# Sheet1.net
KiCad netlist of a schematic drawn in Altium Designer
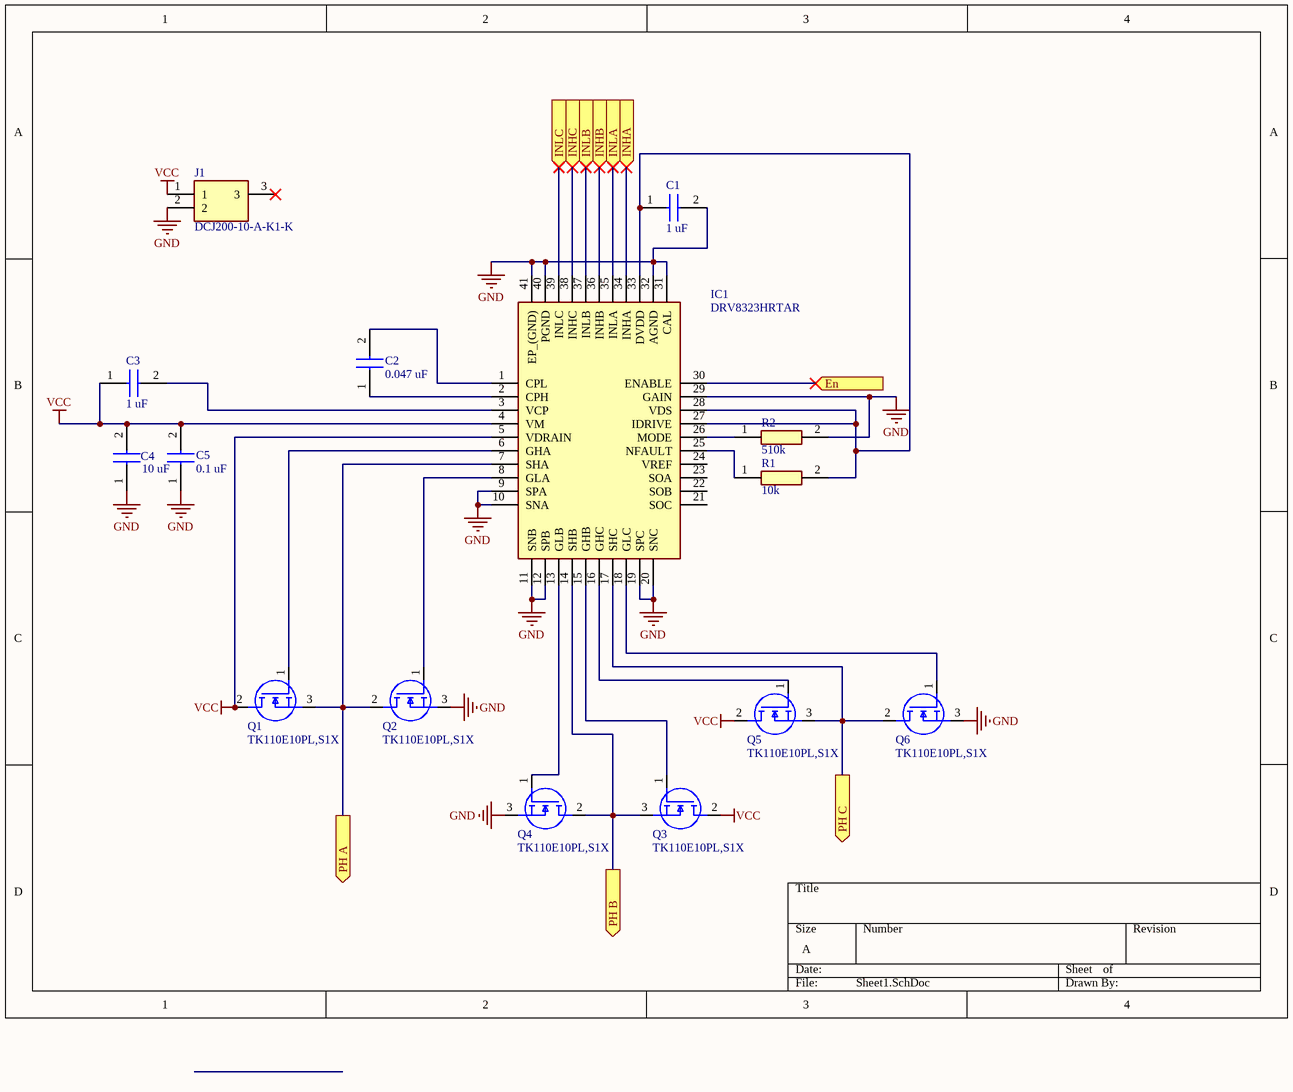
[diagram p0: Sheet1.SchDoc]

(export (version "E")
  (design (tool "Eeschema 10.0.6"))
  (components
    (comp (ref "C1")
      (value "1 uF")
      (footprint "SamacSys:INDC1608X90N")
      (description "Capacitor")
      (fields
        (field (name "MANUFACTURER_PART_NUMBER") "UMK107BJ105KA-T")
        (field (name "MOUSER PART NUMBER") "963-UMK107BJ105KA-T")
      )
      (libsource (lib "*") (part "UMK107BJ105KA-T"))
    )
    (comp (ref "C2")
      (value "0.047 uF")
      (footprint "SamacSys:C0603")
      (description "Capacitor")
      (fields
        (field (name "MANUFACTURER_PART_NUMBER") "C0603C473K5RACTU")
        (field (name "MOUSER PART NUMBER") "80-C0603C473K5R")
      )
      (libsource (lib "*") (part "C0603C473K5RACTU"))
    )
    (comp (ref "C3")
      (value "1 uF")
      (footprint "SamacSys:INDC1608X90N")
      (description "Capacitor")
      (fields
        (field (name "MANUFACTURER_PART_NUMBER") "UMK107BJ105KA-T")
        (field (name "MOUSER PART NUMBER") "963-UMK107BJ105KA-T")
      )
      (libsource (lib "*") (part "UMK107BJ105KA-T"))
    )
    (comp (ref "C4")
      (value "10 uF")
      (footprint "SamacSys:CAPC3216X180N")
      (description "Capacitor")
      (fields
        (field (name "MANUFACTURER_PART_NUMBER") "CL31B106KBHNNNE")
        (field (name "MOUSER PART NUMBER") "187-CL31B106KBHNNNE")
      )
      (libsource (lib "*") (part "CL31B106KBHNNNE"))
    )
    (comp (ref "C5")
      (value "0.1 uF")
      (footprint "SamacSys:CAPC1608X95N")
      (description "Capacitor")
      (fields (field (name "MANUFACTURER_PART_NUMBER") "C0603C104K5RACTU7042"))
      (libsource (lib "*") (part "C0603C104K5RACTU7042"))
    )
    (comp (ref "IC1")
      (value "DRV8323HRTAR")
      (footprint "SamacSys:QFN50P600X600X80-41N-D")
      (description "Integrated Circuit")
      (fields (field (name "MOUSER PART NUMBER") "595-DRV8323HRTAR"))
      (libsource (lib "*") (part "DRV8323HRTAR"))
    )
    (comp (ref "J1")
      (value "DCJ200-10-A-K1-K")
      (footprint "SamacSys:DCJ20010AK1K")
      (description "Connector")
      (fields (field (name "MOUSER PART NUMBER") "640-DCJ200-10-A-K1-K"))
      (libsource (lib "*") (part "DCJ200-10-A-K1-K"))
    )
    (comp (ref "Q1")
      (value "TK110E10PL,S1X")
      (footprint "SamacSys:TO254P465X1016X1935-3P")
      (description "MOSFET (N-Channel)")
      (fields (field (name "MOUSER PART NUMBER") "757-TK110E10PLS1X"))
      (libsource (lib "*") (part "TK110E10PL,S1X"))
    )
    (comp (ref "Q2")
      (value "TK110E10PL,S1X")
      (footprint "SamacSys:TO254P465X1016X1935-3P")
      (description "MOSFET (N-Channel)")
      (fields (field (name "MOUSER PART NUMBER") "757-TK110E10PLS1X"))
      (libsource (lib "*") (part "TK110E10PL,S1X"))
    )
    (comp (ref "Q3")
      (value "TK110E10PL,S1X")
      (footprint "SamacSys:TO254P465X1016X1935-3P")
      (description "MOSFET (N-Channel)")
      (fields (field (name "MOUSER PART NUMBER") "757-TK110E10PLS1X"))
      (libsource (lib "*") (part "TK110E10PL,S1X"))
    )
    (comp (ref "Q4")
      (value "TK110E10PL,S1X")
      (footprint "SamacSys:TO254P465X1016X1935-3P")
      (description "MOSFET (N-Channel)")
      (fields (field (name "MOUSER PART NUMBER") "757-TK110E10PLS1X"))
      (libsource (lib "*") (part "TK110E10PL,S1X"))
    )
    (comp (ref "Q5")
      (value "TK110E10PL,S1X")
      (footprint "SamacSys:TO254P465X1016X1935-3P")
      (description "MOSFET (N-Channel)")
      (fields (field (name "MOUSER PART NUMBER") "757-TK110E10PLS1X"))
      (libsource (lib "*") (part "TK110E10PL,S1X"))
    )
    (comp (ref "Q6")
      (value "TK110E10PL,S1X")
      (footprint "SamacSys:TO254P465X1016X1935-3P")
      (description "MOSFET (N-Channel)")
      (fields (field (name "MOUSER PART NUMBER") "757-TK110E10PLS1X"))
      (libsource (lib "*") (part "TK110E10PL,S1X"))
    )
    (comp (ref "R1")
      (value "10k")
      (footprint "SamacSys:RESC2012X50N")
      (description "Resistor 10K")
      (fields
        (field (name "MANUFACTURER_PART_NUMBER") "CRCW080510K0FKEA")
        (field (name "MOUSER PART NUMBER") "71-CRCW0805-10K-E3")
      )
      (libsource (lib "*") (part "CRCW080510K0FKEA"))
    )
    (comp (ref "R2")
      (value "510k")
      (footprint "SamacSys:RESC3116X65N")
      (description "Resistor 510K")
      (fields
        (field (name "MANUFACTURER_PART_NUMBER") "RC1206FR-07510KL")
        (field (name "MOUSER PART NUMBER") "603-RC1206FR-07510KL")
      )
      (libsource (lib "*") (part "RC1206FR-07510KL"))
    )
  )
  (nets
    (net (code "1") (name "/En") (class "Default")
      (node (ref "IC1") (pin "30") (pinfunction "ENABLE_30") (pintype "passive+no_connect"))
    )
    (net (code "2") (name "/INHA") (class "Default")
      (node (ref "IC1") (pin "34") (pinfunction "INHA_34") (pintype "passive+no_connect"))
    )
    (net (code "3") (name "/INHB") (class "Default")
      (node (ref "IC1") (pin "36") (pinfunction "INHB_36") (pintype "passive+no_connect"))
    )
    (net (code "4") (name "/INHC") (class "Default")
      (node (ref "IC1") (pin "38") (pinfunction "INHC_38") (pintype "passive+no_connect"))
    )
    (net (code "5") (name "/INLA") (class "Default")
      (node (ref "IC1") (pin "35") (pinfunction "INLA_35") (pintype "passive+no_connect"))
    )
    (net (code "6") (name "/INLB") (class "Default")
      (node (ref "IC1") (pin "37") (pinfunction "INLB_37") (pintype "passive+no_connect"))
    )
    (net (code "7") (name "/INLC") (class "Default")
      (node (ref "IC1") (pin "39") (pinfunction "INLC_39") (pintype "passive+no_connect"))
    )
    (net (code "8") (name "/PH A") (class "Default")
      (node (ref "IC1") (pin "7") (pinfunction "SHA_7") (pintype "passive"))
      (node (ref "Q1") (pin "3") (pinfunction "S_3") (pintype "passive"))
      (node (ref "Q2") (pin "2") (pinfunction "D_2") (pintype "passive"))
    )
    (net (code "9") (name "/PH B") (class "Default")
      (node (ref "IC1") (pin "14") (pinfunction "SHB_14") (pintype "passive"))
      (node (ref "Q3") (pin "3") (pinfunction "S_3") (pintype "passive"))
      (node (ref "Q4") (pin "2") (pinfunction "D_2") (pintype "passive"))
    )
    (net (code "10") (name "/PH C") (class "Default")
      (node (ref "IC1") (pin "17") (pinfunction "SHC_17") (pintype "passive"))
      (node (ref "Q5") (pin "3") (pinfunction "S_3") (pintype "passive"))
      (node (ref "Q6") (pin "2") (pinfunction "D_2") (pintype "passive"))
    )
    (net (code "11") (name "GND") (class "Default")
      (node (ref "C1") (pin "2") (pinfunction "2_2") (pintype "passive"))
      (node (ref "C4") (pin "1") (pinfunction "1_1") (pintype "passive"))
      (node (ref "C5") (pin "1") (pinfunction "1_1") (pintype "passive"))
      (node (ref "IC1") (pin "10") (pinfunction "SNA_10") (pintype "passive"))
      (node (ref "IC1") (pin "11") (pinfunction "SNB_11") (pintype "passive"))
      (node (ref "IC1") (pin "12") (pinfunction "SPB_12") (pintype "passive"))
      (node (ref "IC1") (pin "19") (pinfunction "SPC_19") (pintype "passive"))
      (node (ref "IC1") (pin "20") (pinfunction "SNC_20") (pintype "passive"))
      (node (ref "IC1") (pin "29") (pinfunction "GAIN_29") (pintype "passive"))
      (node (ref "IC1") (pin "31") (pinfunction "CAL_31") (pintype "passive"))
      (node (ref "IC1") (pin "32") (pinfunction "AGND_32") (pintype "passive"))
      (node (ref "IC1") (pin "40") (pinfunction "PGND_40") (pintype "passive"))
      (node (ref "IC1") (pin "41") (pinfunction "EP_(GND)_41") (pintype "passive"))
      (node (ref "IC1") (pin "9") (pinfunction "SPA_9") (pintype "passive"))
      (node (ref "J1") (pin "2") (pinfunction "2_2") (pintype "passive"))
      (node (ref "Q2") (pin "3") (pinfunction "S_3") (pintype "passive"))
      (node (ref "Q4") (pin "3") (pinfunction "S_3") (pintype "passive"))
      (node (ref "Q6") (pin "3") (pinfunction "S_3") (pintype "passive"))
      (node (ref "R2") (pin "2") (pinfunction "2_2") (pintype "passive"))
    )
    (net (code "12") (name "Net-(IC1-CPH)") (class "Default")
      (node (ref "C2") (pin "1") (pinfunction "1_1") (pintype "passive"))
      (node (ref "IC1") (pin "2") (pinfunction "CPH_2") (pintype "passive"))
    )
    (net (code "13") (name "Net-(IC1-CPL)") (class "Default")
      (node (ref "C2") (pin "2") (pinfunction "2_2") (pintype "passive"))
      (node (ref "IC1") (pin "1") (pinfunction "CPL_1") (pintype "passive"))
    )
    (net (code "14") (name "Net-(IC1-DVDD)") (class "Default")
      (node (ref "C1") (pin "1") (pinfunction "1_1") (pintype "passive"))
      (node (ref "IC1") (pin "27") (pinfunction "IDRIVE_27") (pintype "passive"))
      (node (ref "IC1") (pin "28") (pinfunction "VDS_28") (pintype "passive"))
      (node (ref "IC1") (pin "33") (pinfunction "DVDD_33") (pintype "passive"))
      (node (ref "R1") (pin "2") (pinfunction "2_2") (pintype "passive"))
    )
    (net (code "15") (name "Net-(IC1-GHA)") (class "Default")
      (node (ref "IC1") (pin "6") (pinfunction "GHA_6") (pintype "passive"))
      (node (ref "Q1") (pin "1") (pinfunction "G_1") (pintype "passive"))
    )
    (net (code "16") (name "Net-(IC1-GHB)") (class "Default")
      (node (ref "IC1") (pin "15") (pinfunction "GHB_15") (pintype "passive"))
      (node (ref "Q3") (pin "1") (pinfunction "G_1") (pintype "passive"))
    )
    (net (code "17") (name "Net-(IC1-GHC)") (class "Default")
      (node (ref "IC1") (pin "16") (pinfunction "GHC_16") (pintype "passive"))
      (node (ref "Q5") (pin "1") (pinfunction "G_1") (pintype "passive"))
    )
    (net (code "18") (name "Net-(IC1-GLA)") (class "Default")
      (node (ref "IC1") (pin "8") (pinfunction "GLA_8") (pintype "passive"))
      (node (ref "Q2") (pin "1") (pinfunction "G_1") (pintype "passive"))
    )
    (net (code "19") (name "Net-(IC1-GLB)") (class "Default")
      (node (ref "IC1") (pin "13") (pinfunction "GLB_13") (pintype "passive"))
      (node (ref "Q4") (pin "1") (pinfunction "G_1") (pintype "passive"))
    )
    (net (code "20") (name "Net-(IC1-GLC)") (class "Default")
      (node (ref "IC1") (pin "18") (pinfunction "GLC_18") (pintype "passive"))
      (node (ref "Q6") (pin "1") (pinfunction "G_1") (pintype "passive"))
    )
    (net (code "21") (name "Net-(IC1-MODE)") (class "Default")
      (node (ref "IC1") (pin "26") (pinfunction "MODE_26") (pintype "passive"))
      (node (ref "R2") (pin "1") (pinfunction "1_1") (pintype "passive"))
    )
    (net (code "22") (name "Net-(IC1-NFAULT)") (class "Default")
      (node (ref "IC1") (pin "25") (pinfunction "NFAULT_25") (pintype "passive"))
      (node (ref "R1") (pin "1") (pinfunction "1_1") (pintype "passive"))
    )
    (net (code "23") (name "Net-(IC1-VCP)") (class "Default")
      (node (ref "C3") (pin "2") (pinfunction "2_2") (pintype "passive"))
      (node (ref "IC1") (pin "3") (pinfunction "VCP_3") (pintype "passive"))
    )
    (net (code "24") (name "VCC") (class "Default")
      (node (ref "C3") (pin "1") (pinfunction "1_1") (pintype "passive"))
      (node (ref "C4") (pin "2") (pinfunction "2_2") (pintype "passive"))
      (node (ref "C5") (pin "2") (pinfunction "2_2") (pintype "passive"))
      (node (ref "IC1") (pin "4") (pinfunction "VM_4") (pintype "passive"))
      (node (ref "IC1") (pin "5") (pinfunction "VDRAIN_5") (pintype "passive"))
      (node (ref "J1") (pin "1") (pinfunction "1_1") (pintype "passive"))
      (node (ref "Q1") (pin "2") (pinfunction "D_2") (pintype "passive"))
      (node (ref "Q3") (pin "2") (pinfunction "D_2") (pintype "passive"))
      (node (ref "Q5") (pin "2") (pinfunction "D_2") (pintype "passive"))
    )
    (net (code "25") (name "unconnected-(IC1-SOA-Pad23)") (class "Default")
      (node (ref "IC1") (pin "23") (pinfunction "SOA_23") (pintype "passive"))
    )
    (net (code "26") (name "unconnected-(IC1-SOB-Pad22)") (class "Default")
      (node (ref "IC1") (pin "22") (pinfunction "SOB_22") (pintype "passive"))
    )
    (net (code "27") (name "unconnected-(IC1-SOC-Pad21)") (class "Default")
      (node (ref "IC1") (pin "21") (pinfunction "SOC_21") (pintype "passive"))
    )
    (net (code "28") (name "unconnected-(IC1-VREF-Pad24)") (class "Default")
      (node (ref "IC1") (pin "24") (pinfunction "VREF_24") (pintype "passive"))
    )
    (net (code "29") (name "unconnected-(J1-Pad3)") (class "Default")
      (node (ref "J1") (pin "3") (pinfunction "3_3") (pintype "passive+no_connect"))
    )
  )
)
